# ArduTouch_stereo_v1_2c.net
KiCad netlist of a schematic drawn in EAGLE
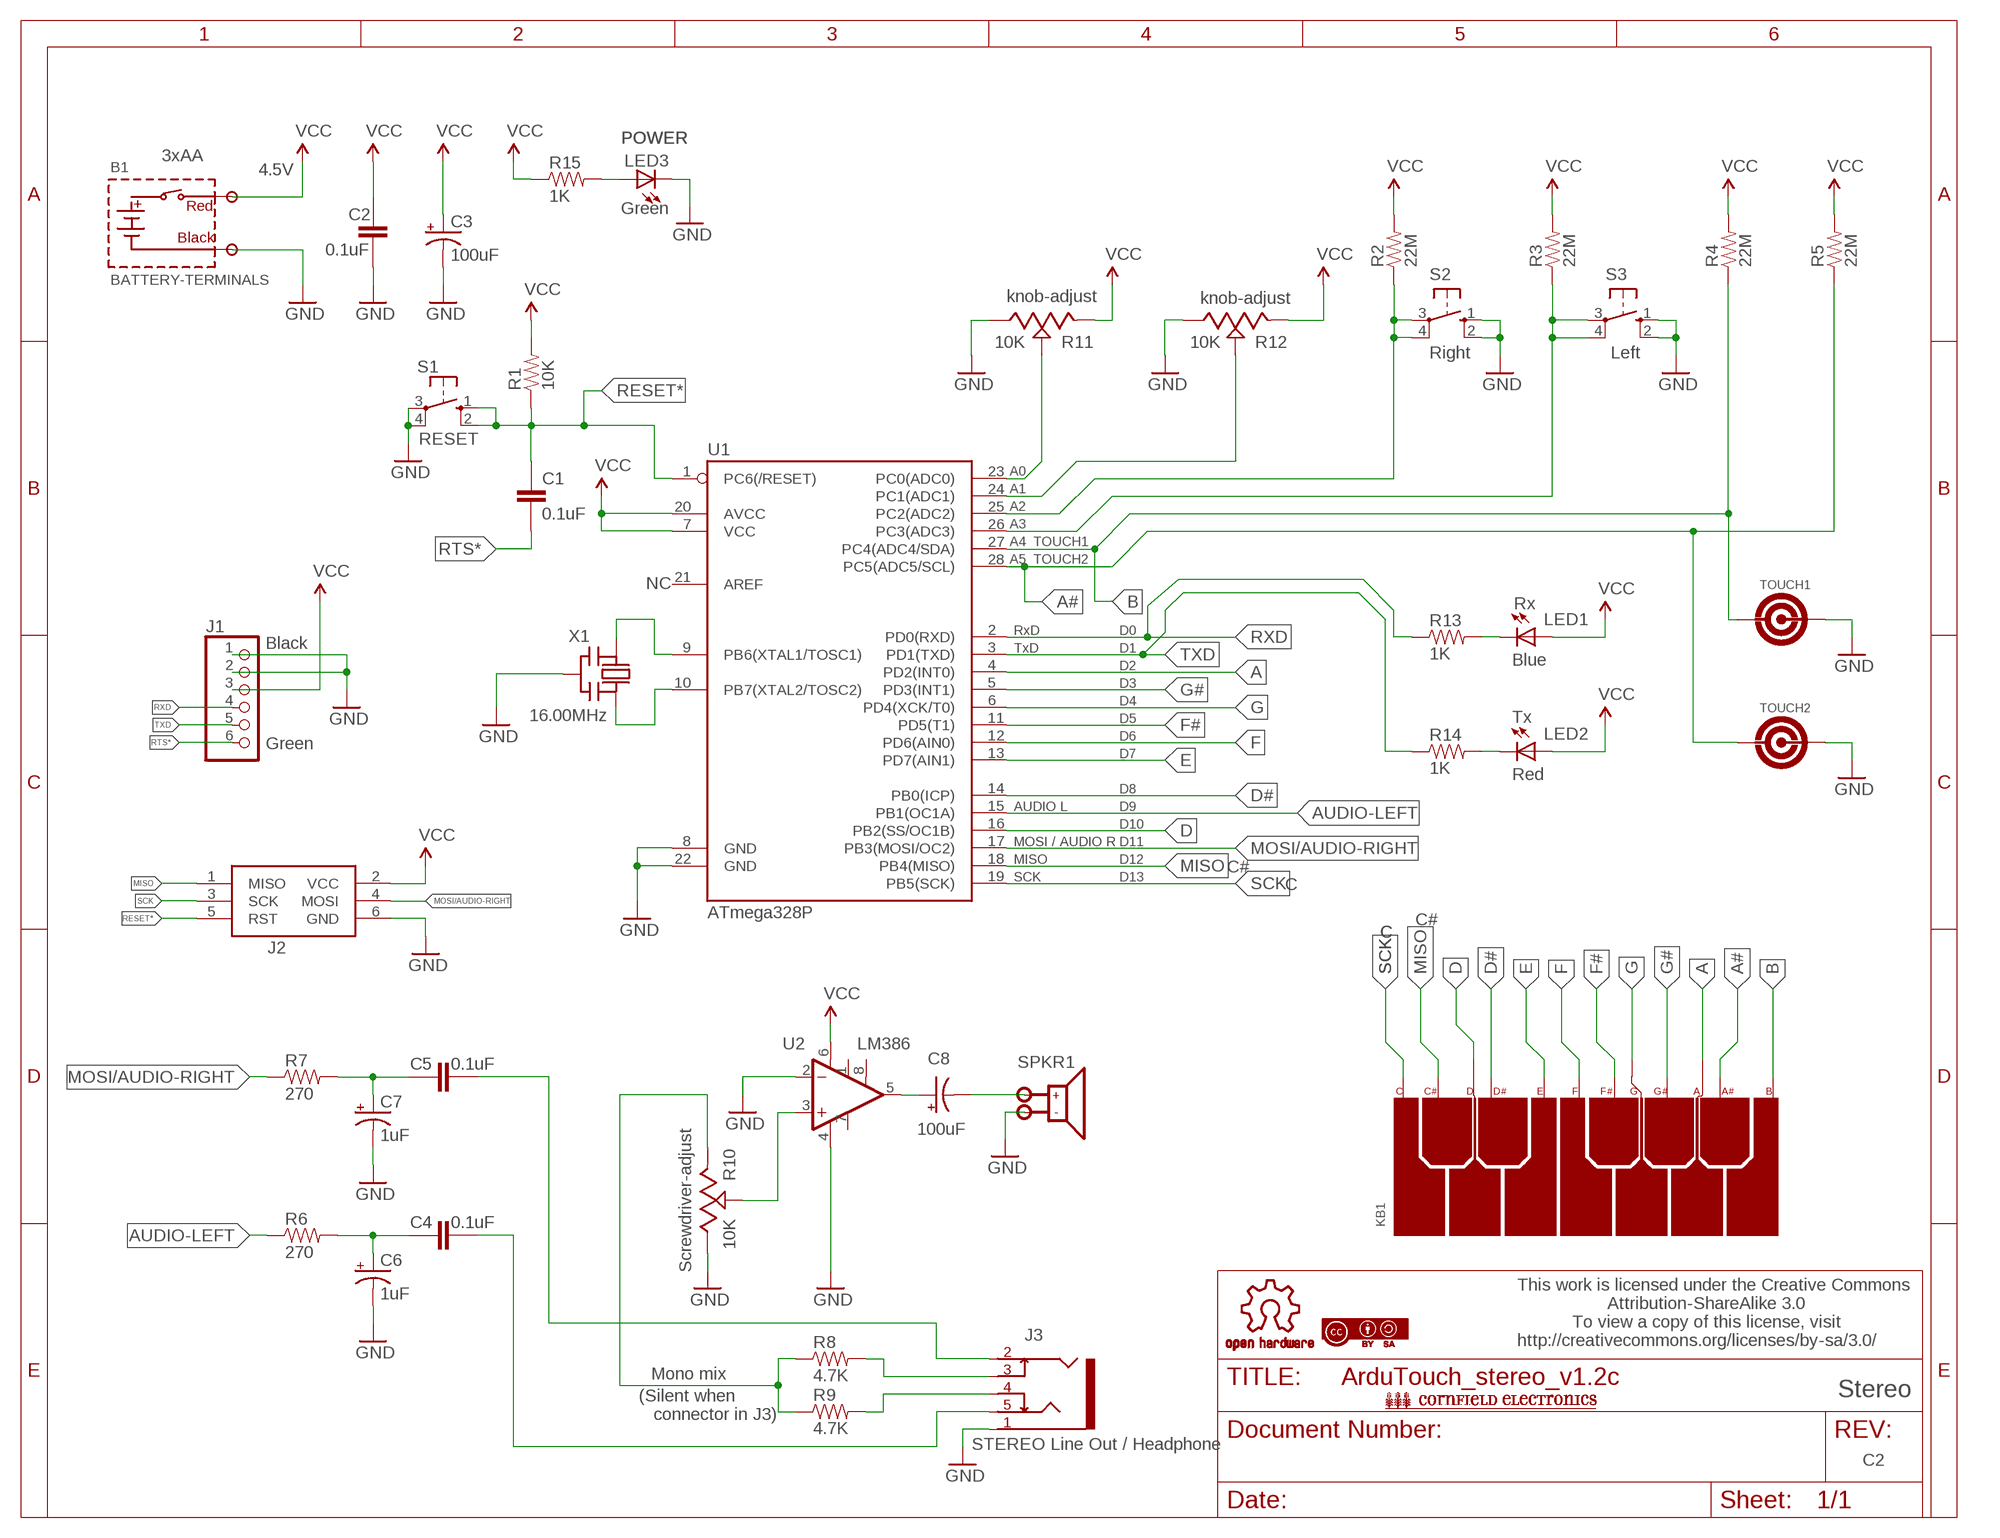
[diagram p0: schematic, sheet 1]

(export (version "E")
  (design (tool "Eeschema 10.0.6"))
  (components
    (comp (ref "B1")
      (value "BATTERY-TERMINALS")
      (footprint "eagle-import:BATTERY-TERMINALS")
      (libsource (lib "eagle-import") (part "BATTERY-TERMINALS"))
    )
    (comp (ref "C1")
      (value "0.1uF")
      (footprint "eagle-import:CAP-PTH-SMALL")
      (libsource (lib "eagle-import") (part "CAPPTH"))
    )
    (comp (ref "C2")
      (value "0.1uF")
      (footprint "eagle-import:CAP-PTH-SMALL")
      (libsource (lib "eagle-import") (part "CAPPTH"))
    )
    (comp (ref "C3")
      (value "100uF")
      (footprint "eagle-import:CPOL-RADIAL-10UF-25V")
      (libsource (lib "eagle-import") (part "CPOL-RADIAL-10UF-25V"))
    )
    (comp (ref "C4")
      (value "0.1uF")
      (footprint "eagle-import:CAP-PTH-SMALL")
      (libsource (lib "eagle-import") (part "CAPPTH"))
    )
    (comp (ref "C5")
      (value "0.1uF")
      (footprint "eagle-import:CAP-PTH-SMALL")
      (libsource (lib "eagle-import") (part "CAPPTH"))
    )
    (comp (ref "C6")
      (value "1uF")
      (footprint "eagle-import:CPOL-RADIAL-10UF-25V")
      (libsource (lib "eagle-import") (part "CPOL-RADIAL-10UF-25V"))
    )
    (comp (ref "C7")
      (value "1uF")
      (footprint "eagle-import:CPOL-RADIAL-10UF-25V")
      (libsource (lib "eagle-import") (part "CPOL-RADIAL-10UF-25V"))
    )
    (comp (ref "C8")
      (value "100uF")
      (footprint "eagle-import:CPOL-RADIAL-10UF-25V")
      (libsource (lib "eagle-import") (part "CPOL-RADIAL-10UF-25V"))
    )
    (comp (ref "J1")
      (value "PINHD-1X6LOCK")
      (footprint "eagle-import:1X06-BIGLOCK")
      (libsource (lib "eagle-import") (part "PINHD-1X6LOCK"))
    )
    (comp (ref "J2")
      (value "ISP")
      (footprint "eagle-import:AVRISP")
      (libsource (lib "eagle-import") (part "AVRISP-6"))
    )
    (comp (ref "J3")
      (value "STEREO-AUDIO-3.5MM-SWITCHED")
      (footprint "eagle-import:STEREO-AUDIO-3.5MM-SWITCHED")
      (libsource (lib "eagle-import") (part "STEREO-AUDIO-3.5MM-SWITCHED"))
    )
    (comp (ref "KB1")
      (value "PCB-KEYBOARD4")
      (footprint "eagle-import:PCB-KEYBOARD4")
      (libsource (lib "eagle-import") (part "PCB-KEYBOARD4"))
    )
    (comp (ref "LED1")
      (value "Blue")
      (footprint "eagle-import:LED5MM")
      (libsource (lib "eagle-import") (part "LED5MM"))
    )
    (comp (ref "LED2")
      (value "Red")
      (footprint "eagle-import:LED5MM")
      (libsource (lib "eagle-import") (part "LED5MM"))
    )
    (comp (ref "LED3")
      (value "Green")
      (footprint "eagle-import:LED5MM")
      (libsource (lib "eagle-import") (part "LED5MM"))
    )
    (comp (ref "R1")
      (value "10K")
      (footprint "eagle-import:AXIAL-0.4")
      (libsource (lib "eagle-import") (part "RESISTORPTH-1/4W"))
    )
    (comp (ref "R2")
      (value "22M")
      (footprint "eagle-import:AXIAL-0.4")
      (libsource (lib "eagle-import") (part "RESISTORPTH-1/4W"))
    )
    (comp (ref "R3")
      (value "22M")
      (footprint "eagle-import:AXIAL-0.4")
      (libsource (lib "eagle-import") (part "RESISTORPTH-1/4W"))
    )
    (comp (ref "R4")
      (value "22M")
      (footprint "eagle-import:AXIAL-0.4")
      (libsource (lib "eagle-import") (part "RESISTORPTH-1/4W"))
    )
    (comp (ref "R5")
      (value "22M")
      (footprint "eagle-import:AXIAL-0.4")
      (libsource (lib "eagle-import") (part "RESISTORPTH-1/4W"))
    )
    (comp (ref "R6")
      (value "270")
      (footprint "eagle-import:AXIAL-0.4")
      (libsource (lib "eagle-import") (part "RESISTORPTH-1/4W"))
    )
    (comp (ref "R7")
      (value "270")
      (footprint "eagle-import:AXIAL-0.4")
      (libsource (lib "eagle-import") (part "RESISTORPTH-1/4W"))
    )
    (comp (ref "R8")
      (value "4.7K")
      (footprint "eagle-import:AXIAL-0.4")
      (libsource (lib "eagle-import") (part "RESISTORPTH-1/4W"))
    )
    (comp (ref "R9")
      (value "4.7K")
      (footprint "eagle-import:AXIAL-0.4")
      (libsource (lib "eagle-import") (part "RESISTORPTH-1/4W"))
    )
    (comp (ref "R10")
      (value "10K")
      (footprint "eagle-import:TRIMPOT-3319P-1")
      (libsource (lib "eagle-import") (part "TRIMPOT-3319P-1"))
    )
    (comp (ref "R11")
      (value "10K")
      (footprint "eagle-import:TRIMPOT-72PTR")
      (libsource (lib "eagle-import") (part "TRIMPOT-72PTR"))
    )
    (comp (ref "R12")
      (value "10K")
      (footprint "eagle-import:TRIMPOT-72PTR")
      (libsource (lib "eagle-import") (part "TRIMPOT-72PTR"))
    )
    (comp (ref "R13")
      (value "1K")
      (footprint "eagle-import:AXIAL-0.4")
      (libsource (lib "eagle-import") (part "RESISTORPTH-1/4W"))
    )
    (comp (ref "R14")
      (value "1K")
      (footprint "eagle-import:AXIAL-0.4")
      (libsource (lib "eagle-import") (part "RESISTORPTH-1/4W"))
    )
    (comp (ref "R15")
      (value "1K")
      (footprint "eagle-import:AXIAL-0.4")
      (libsource (lib "eagle-import") (part "RESISTORPTH-1/4W"))
    )
    (comp (ref "S1")
      (value "TACTILE_SWITCH_6.3MM")
      (footprint "eagle-import:TACTILE_SWITCH_6.3MM")
      (libsource (lib "eagle-import") (part "TACTILE_SWITCH_6.3MM"))
    )
    (comp (ref "S2")
      (value "TACTILE_SWITCH_6.3MM")
      (footprint "eagle-import:TACTILE_SWITCH_6.3MM")
      (libsource (lib "eagle-import") (part "TACTILE_SWITCH_6.3MM"))
    )
    (comp (ref "S3")
      (value "TACTILE_SWITCH_6.3MM")
      (footprint "eagle-import:TACTILE_SWITCH_6.3MM")
      (libsource (lib "eagle-import") (part "TACTILE_SWITCH_6.3MM"))
    )
    (comp (ref "SPKR1")
      (value "SPEAKER-TERMINALS")
      (footprint "eagle-import:SPEAKER-TERMINALS")
      (libsource (lib "eagle-import") (part "SPEAKER-TERMINALS"))
    )
    (comp (ref "TOUCH1")
      (value "PCB-TOUCHPAD2")
      (footprint "eagle-import:PCB-TOUCHPAD2")
      (libsource (lib "eagle-import") (part "PCB-TOUCHPAD2"))
    )
    (comp (ref "TOUCH2")
      (value "PCB-TOUCHPAD2")
      (footprint "eagle-import:PCB-TOUCHPAD2")
      (libsource (lib "eagle-import") (part "PCB-TOUCHPAD2"))
    )
    (comp (ref "U$1")
      (value "OSH-LOGO")
      (footprint "eagle-import:OSH-LOGO")
      (libsource (lib "eagle-import") (part "OSH-LOGO"))
    )
    (comp (ref "U$2")
      (value "CC-BY-SA-LOGO2")
      (footprint "eagle-import:CC-BY-SA-LOGO2")
      (libsource (lib "eagle-import") (part "CC-BY-SA-LOGO2"))
    )
    (comp (ref "U$3")
      (value "CORNFIELD-LOGO")
      (footprint "eagle-import:CORNFIELD-LOGO")
      (libsource (lib "eagle-import") (part "CORNFIELD-LOGO"))
    )
    (comp (ref "U1")
      (value "ATmega328P")
      (footprint "eagle-import:DIL28-3")
      (libsource (lib "eagle-import") (part "ATMEGA328P_PDIP"))
    )
    (comp (ref "U2")
      (value "LM386")
      (footprint "eagle-import:DIP08")
      (libsource (lib "eagle-import") (part "LM386"))
    )
    (comp (ref "X1")
      (value "16.00MHz")
      (footprint "eagle-import:CERM_OSC")
      (libsource (lib "eagle-import") (part "CERMOSCILL-THM"))
    )
  )
  (nets
    (net (code "1") (name "A") (class "Default")
      (node (ref "KB1") (pin "A") (pinfunction "A_A") (pintype "bidirectional"))
      (node (ref "U1") (pin "4") (pinfunction "PD2(INT0)_4") (pintype "bidirectional"))
    )
    (net (code "2") (name "A#") (class "Default")
      (node (ref "KB1") (pin "A#") (pinfunction "A#_A#") (pintype "bidirectional"))
      (node (ref "R5") (pin "P$1") (pinfunction "1_P$1") (pintype "passive"))
      (node (ref "TOUCH2") (pin "1") (pinfunction "1_1") (pintype "bidirectional"))
      (node (ref "U1") (pin "28") (pinfunction "PC5(ADC5/SCL)_28") (pintype "bidirectional"))
    )
    (net (code "3") (name "AUDIO-LEFT") (class "Default")
      (node (ref "R6") (pin "P$1") (pinfunction "1_P$1") (pintype "passive"))
      (node (ref "U1") (pin "15") (pinfunction "PB1(OC1A)_15") (pintype "bidirectional"))
    )
    (net (code "4") (name "B") (class "Default")
      (node (ref "KB1") (pin "B") (pinfunction "B_B") (pintype "bidirectional"))
      (node (ref "R4") (pin "P$1") (pinfunction "1_P$1") (pintype "passive"))
      (node (ref "TOUCH1") (pin "1") (pinfunction "1_1") (pintype "bidirectional"))
      (node (ref "U1") (pin "27") (pinfunction "PC4(ADC4/SDA)_27") (pintype "bidirectional"))
    )
    (net (code "5") (name "D") (class "Default")
      (node (ref "KB1") (pin "D") (pinfunction "D_D") (pintype "bidirectional"))
      (node (ref "U1") (pin "16") (pinfunction "PB2(SS/OC1B)_16") (pintype "bidirectional"))
    )
    (net (code "6") (name "D#") (class "Default")
      (node (ref "KB1") (pin "D#") (pinfunction "D#_D#") (pintype "bidirectional"))
      (node (ref "U1") (pin "14") (pinfunction "PB0(ICP)_14") (pintype "bidirectional"))
    )
    (net (code "7") (name "E") (class "Default")
      (node (ref "KB1") (pin "E") (pinfunction "E_E") (pintype "bidirectional"))
      (node (ref "U1") (pin "13") (pinfunction "PD7(AIN1)_13") (pintype "bidirectional"))
    )
    (net (code "8") (name "F") (class "Default")
      (node (ref "KB1") (pin "F") (pinfunction "F_F") (pintype "bidirectional"))
      (node (ref "U1") (pin "12") (pinfunction "PD6(AIN0)_12") (pintype "bidirectional"))
    )
    (net (code "9") (name "F#") (class "Default")
      (node (ref "KB1") (pin "F#") (pinfunction "F#_F#") (pintype "bidirectional"))
      (node (ref "U1") (pin "11") (pinfunction "PD5(T1)_11") (pintype "bidirectional"))
    )
    (net (code "10") (name "G") (class "Default")
      (node (ref "KB1") (pin "G") (pinfunction "G_G") (pintype "bidirectional"))
      (node (ref "U1") (pin "6") (pinfunction "PD4(XCK/T0)_6") (pintype "bidirectional"))
    )
    (net (code "11") (name "G#") (class "Default")
      (node (ref "KB1") (pin "G#") (pinfunction "G#_G#") (pintype "bidirectional"))
      (node (ref "U1") (pin "5") (pinfunction "PD3(INT1)_5") (pintype "bidirectional"))
    )
    (net (code "12") (name "GND") (class "Default")
      (node (ref "B1") (pin "-") (pinfunction "-_-") (pintype "bidirectional"))
      (node (ref "C2") (pin "2") (pinfunction "2_2") (pintype "passive"))
      (node (ref "C3") (pin "-") (pinfunction "-_-") (pintype "passive"))
      (node (ref "C6") (pin "-") (pinfunction "-_-") (pintype "passive"))
      (node (ref "C7") (pin "-") (pinfunction "-_-") (pintype "passive"))
      (node (ref "J1") (pin "1") (pinfunction "1_1") (pintype "passive"))
      (node (ref "J1") (pin "2") (pinfunction "2_2") (pintype "passive"))
      (node (ref "J2") (pin "6") (pinfunction "GND_6") (pintype "power_in"))
      (node (ref "J3") (pin "1") (pinfunction "1_1") (pintype "bidirectional"))
      (node (ref "LED3") (pin "K") (pinfunction "C_K") (pintype "passive"))
      (node (ref "R10") (pin "A") (pinfunction "A_A") (pintype "passive"))
      (node (ref "R11") (pin "3") (pinfunction "A_3") (pintype "passive"))
      (node (ref "R12") (pin "3") (pinfunction "A_3") (pintype "passive"))
      (node (ref "S1") (pin "3") (pinfunction "3_3") (pintype "passive"))
      (node (ref "S1") (pin "4") (pinfunction "4_4") (pintype "passive"))
      (node (ref "S2") (pin "1") (pinfunction "1_1") (pintype "passive"))
      (node (ref "S2") (pin "2") (pinfunction "2_2") (pintype "passive"))
      (node (ref "S3") (pin "1") (pinfunction "1_1") (pintype "passive"))
      (node (ref "S3") (pin "2") (pinfunction "2_2") (pintype "passive"))
      (node (ref "SPKR1") (pin "-") (pinfunction "-_-") (pintype "bidirectional"))
      (node (ref "TOUCH1") (pin "2") (pinfunction "2_2") (pintype "bidirectional"))
      (node (ref "TOUCH2") (pin "2") (pinfunction "2_2") (pintype "bidirectional"))
      (node (ref "U1") (pin "22") (pinfunction "GND_22") (pintype "bidirectional"))
      (node (ref "U1") (pin "8") (pinfunction "GND_8") (pintype "bidirectional"))
      (node (ref "U2") (pin "2") (pinfunction "-IN_2") (pintype "input"))
      (node (ref "U2") (pin "4") (pinfunction "V-_4") (pintype "power_in"))
      (node (ref "X1") (pin "P$2") (pinfunction "GND_P$2") (pintype "bidirectional"))
    )
    (net (code "13") (name "MISO") (class "Default")
      (node (ref "J2") (pin "1") (pinfunction "MISO_1") (pintype "input"))
      (node (ref "KB1") (pin "C#") (pinfunction "C#_C#") (pintype "bidirectional"))
      (node (ref "U1") (pin "18") (pinfunction "PB4(MISO)_18") (pintype "bidirectional"))
    )
    (net (code "14") (name "MOSI{slash}AUDIO-RIGHT") (class "Default")
      (node (ref "J2") (pin "4") (pinfunction "MOSI_4") (pintype "output"))
      (node (ref "R7") (pin "P$1") (pinfunction "1_P$1") (pintype "passive"))
      (node (ref "U1") (pin "17") (pinfunction "PB3(MOSI/OC2)_17") (pintype "bidirectional"))
    )
    (net (code "15") (name "Net-(C4-Pad2)") (class "Default")
      (node (ref "C4") (pin "2") (pinfunction "2_2") (pintype "passive"))
      (node (ref "J3") (pin "5") (pinfunction "5_5") (pintype "bidirectional"))
    )
    (net (code "16") (name "Net-(C5-Pad2)") (class "Default")
      (node (ref "C5") (pin "2") (pinfunction "2_2") (pintype "passive"))
      (node (ref "J3") (pin "2") (pinfunction "2_2") (pintype "bidirectional"))
    )
    (net (code "17") (name "Net-(C8-Pad-)") (class "Default")
      (node (ref "C8") (pin "-") (pinfunction "-_-") (pintype "passive"))
      (node (ref "SPKR1") (pin "+") (pinfunction "+_+") (pintype "bidirectional"))
    )
    (net (code "18") (name "Net-(LED1-C)") (class "Default")
      (node (ref "LED1") (pin "K") (pinfunction "C_K") (pintype "passive"))
      (node (ref "R13") (pin "P$2") (pinfunction "2_P$2") (pintype "passive"))
    )
    (net (code "19") (name "Net-(LED2-C)") (class "Default")
      (node (ref "LED2") (pin "K") (pinfunction "C_K") (pintype "passive"))
      (node (ref "R14") (pin "P$2") (pinfunction "2_P$2") (pintype "passive"))
    )
    (net (code "20") (name "Net-(R2-1)") (class "Default")
      (node (ref "R2") (pin "P$1") (pinfunction "1_P$1") (pintype "passive"))
      (node (ref "S2") (pin "3") (pinfunction "3_3") (pintype "passive"))
      (node (ref "S2") (pin "4") (pinfunction "4_4") (pintype "passive"))
      (node (ref "U1") (pin "25") (pinfunction "PC2(ADC2)_25") (pintype "bidirectional"))
    )
    (net (code "21") (name "Net-(R3-1)") (class "Default")
      (node (ref "R3") (pin "P$1") (pinfunction "1_P$1") (pintype "passive"))
      (node (ref "S3") (pin "3") (pinfunction "3_3") (pintype "passive"))
      (node (ref "S3") (pin "4") (pinfunction "4_4") (pintype "passive"))
      (node (ref "U1") (pin "26") (pinfunction "PC3(ADC3)_26") (pintype "bidirectional"))
    )
    (net (code "22") (name "Net-(R6-2)") (class "Default")
      (node (ref "C4") (pin "1") (pinfunction "1_1") (pintype "passive"))
      (node (ref "C6") (pin "+") (pinfunction "+_+") (pintype "passive"))
      (node (ref "R6") (pin "P$2") (pinfunction "2_P$2") (pintype "passive"))
    )
    (net (code "23") (name "Net-(R7-2)") (class "Default")
      (node (ref "C5") (pin "1") (pinfunction "1_1") (pintype "passive"))
      (node (ref "C7") (pin "+") (pinfunction "+_+") (pintype "passive"))
      (node (ref "R7") (pin "P$2") (pinfunction "2_P$2") (pintype "passive"))
    )
    (net (code "24") (name "Net-(R8-1)") (class "Default")
      (node (ref "R10") (pin "E") (pinfunction "E_E") (pintype "passive"))
      (node (ref "R8") (pin "P$1") (pinfunction "1_P$1") (pintype "passive"))
      (node (ref "R9") (pin "P$1") (pinfunction "1_P$1") (pintype "passive"))
    )
    (net (code "25") (name "Net-(R8-2)") (class "Default")
      (node (ref "J3") (pin "3") (pinfunction "3_3") (pintype "bidirectional"))
      (node (ref "R8") (pin "P$2") (pinfunction "2_P$2") (pintype "passive"))
    )
    (net (code "26") (name "Net-(R9-2)") (class "Default")
      (node (ref "J3") (pin "4") (pinfunction "4_4") (pintype "bidirectional"))
      (node (ref "R9") (pin "P$2") (pinfunction "2_P$2") (pintype "passive"))
    )
    (net (code "27") (name "Net-(R11-S)") (class "Default")
      (node (ref "R11") (pin "2") (pinfunction "S_2") (pintype "passive"))
      (node (ref "U1") (pin "23") (pinfunction "PC0(ADC0)_23") (pintype "bidirectional"))
    )
    (net (code "28") (name "Net-(R12-S)") (class "Default")
      (node (ref "R12") (pin "2") (pinfunction "S_2") (pintype "passive"))
      (node (ref "U1") (pin "24") (pinfunction "PC1(ADC1)_24") (pintype "bidirectional"))
    )
    (net (code "29") (name "Net-(R15-2)") (class "Default")
      (node (ref "LED3") (pin "A") (pinfunction "A_A") (pintype "passive"))
      (node (ref "R15") (pin "P$2") (pinfunction "2_P$2") (pintype "passive"))
    )
    (net (code "30") (name "Net-(U1-PB6(XTAL1{slash}TOSC1))") (class "Default")
      (node (ref "U1") (pin "9") (pinfunction "PB6(XTAL1/TOSC1)_9") (pintype "bidirectional"))
      (node (ref "X1") (pin "P$1") (pinfunction "IN_P$1") (pintype "bidirectional"))
    )
    (net (code "31") (name "Net-(U1-PB7(XTAL2{slash}TOSC2))") (class "Default")
      (node (ref "U1") (pin "10") (pinfunction "PB7(XTAL2/TOSC2)_10") (pintype "bidirectional"))
      (node (ref "X1") (pin "P$3") (pinfunction "OUT_P$3") (pintype "bidirectional"))
    )
    (net (code "32") (name "Net-(U2-+IN)") (class "Default")
      (node (ref "R10") (pin "S") (pinfunction "S_S") (pintype "passive"))
      (node (ref "U2") (pin "3") (pinfunction "+IN_3") (pintype "input"))
    )
    (net (code "33") (name "Net-(U2-OUT)") (class "Default")
      (node (ref "C8") (pin "+") (pinfunction "+_+") (pintype "passive"))
      (node (ref "U2") (pin "5") (pinfunction "OUT_5") (pintype "output"))
    )
    (net (code "34") (name "RESET*") (class "Default")
      (node (ref "C1") (pin "1") (pinfunction "1_1") (pintype "passive"))
      (node (ref "J2") (pin "5") (pinfunction "RST_5") (pintype "output"))
      (node (ref "R1") (pin "P$1") (pinfunction "1_P$1") (pintype "passive"))
      (node (ref "S1") (pin "1") (pinfunction "1_1") (pintype "passive"))
      (node (ref "S1") (pin "2") (pinfunction "2_2") (pintype "passive"))
      (node (ref "U1") (pin "1") (pinfunction "PC6(/RESET)_1") (pintype "bidirectional"))
    )
    (net (code "35") (name "RTS*") (class "Default")
      (node (ref "C1") (pin "2") (pinfunction "2_2") (pintype "passive"))
      (node (ref "J1") (pin "6") (pinfunction "6_6") (pintype "passive"))
    )
    (net (code "36") (name "RXD") (class "Default")
      (node (ref "J1") (pin "4") (pinfunction "4_4") (pintype "passive"))
      (node (ref "R13") (pin "P$1") (pinfunction "1_P$1") (pintype "passive"))
      (node (ref "U1") (pin "2") (pinfunction "PD0(RXD)_2") (pintype "bidirectional"))
    )
    (net (code "37") (name "SCK") (class "Default")
      (node (ref "J2") (pin "3") (pinfunction "SCK_3") (pintype "output"))
      (node (ref "KB1") (pin "C") (pinfunction "C_C") (pintype "bidirectional"))
      (node (ref "U1") (pin "19") (pinfunction "PB5(SCK)_19") (pintype "bidirectional"))
    )
    (net (code "38") (name "TXD") (class "Default")
      (node (ref "J1") (pin "5") (pinfunction "5_5") (pintype "passive"))
      (node (ref "R14") (pin "P$1") (pinfunction "1_P$1") (pintype "passive"))
      (node (ref "U1") (pin "3") (pinfunction "PD1(TXD)_3") (pintype "bidirectional"))
    )
    (net (code "39") (name "VCC") (class "Default")
      (node (ref "B1") (pin "+") (pinfunction "+_+") (pintype "bidirectional"))
      (node (ref "C2") (pin "1") (pinfunction "1_1") (pintype "passive"))
      (node (ref "C3") (pin "+") (pinfunction "+_+") (pintype "passive"))
      (node (ref "J1") (pin "3") (pinfunction "3_3") (pintype "passive"))
      (node (ref "J2") (pin "2") (pinfunction "VCC_2") (pintype "power_in"))
      (node (ref "LED1") (pin "A") (pinfunction "A_A") (pintype "passive"))
      (node (ref "LED2") (pin "A") (pinfunction "A_A") (pintype "passive"))
      (node (ref "R1") (pin "P$2") (pinfunction "2_P$2") (pintype "passive"))
      (node (ref "R11") (pin "1") (pinfunction "E_1") (pintype "passive"))
      (node (ref "R12") (pin "1") (pinfunction "E_1") (pintype "passive"))
      (node (ref "R15") (pin "P$1") (pinfunction "1_P$1") (pintype "passive"))
      (node (ref "R2") (pin "P$2") (pinfunction "2_P$2") (pintype "passive"))
      (node (ref "R3") (pin "P$2") (pinfunction "2_P$2") (pintype "passive"))
      (node (ref "R4") (pin "P$2") (pinfunction "2_P$2") (pintype "passive"))
      (node (ref "R5") (pin "P$2") (pinfunction "2_P$2") (pintype "passive"))
      (node (ref "U1") (pin "20") (pinfunction "AVCC_20") (pintype "bidirectional"))
      (node (ref "U1") (pin "7") (pinfunction "VCC_7") (pintype "bidirectional"))
      (node (ref "U2") (pin "6") (pinfunction "V+_6") (pintype "power_in"))
    )
    (net (code "40") (name "unconnected-(U1-AREF-Pad21)") (class "Default")
      (node (ref "U1") (pin "21") (pinfunction "AREF_21") (pintype "bidirectional"))
    )
    (net (code "41") (name "unconnected-(U2-BP-Pad7)") (class "Default")
      (node (ref "U2") (pin "7") (pinfunction "BP_7") (pintype "bidirectional"))
    )
    (net (code "42") (name "unconnected-(U2-GAIN-Pad1)") (class "Default")
      (node (ref "U2") (pin "1") (pinfunction "GAIN_1") (pintype "bidirectional"))
    )
    (net (code "43") (name "unconnected-(U2-GAIN-Pad8)") (class "Default")
      (node (ref "U2") (pin "8") (pinfunction "GAIN_8") (pintype "bidirectional"))
    )
  )
)
